# motor0.net
KiCad netlist of a schematic drawn in Altium Designer
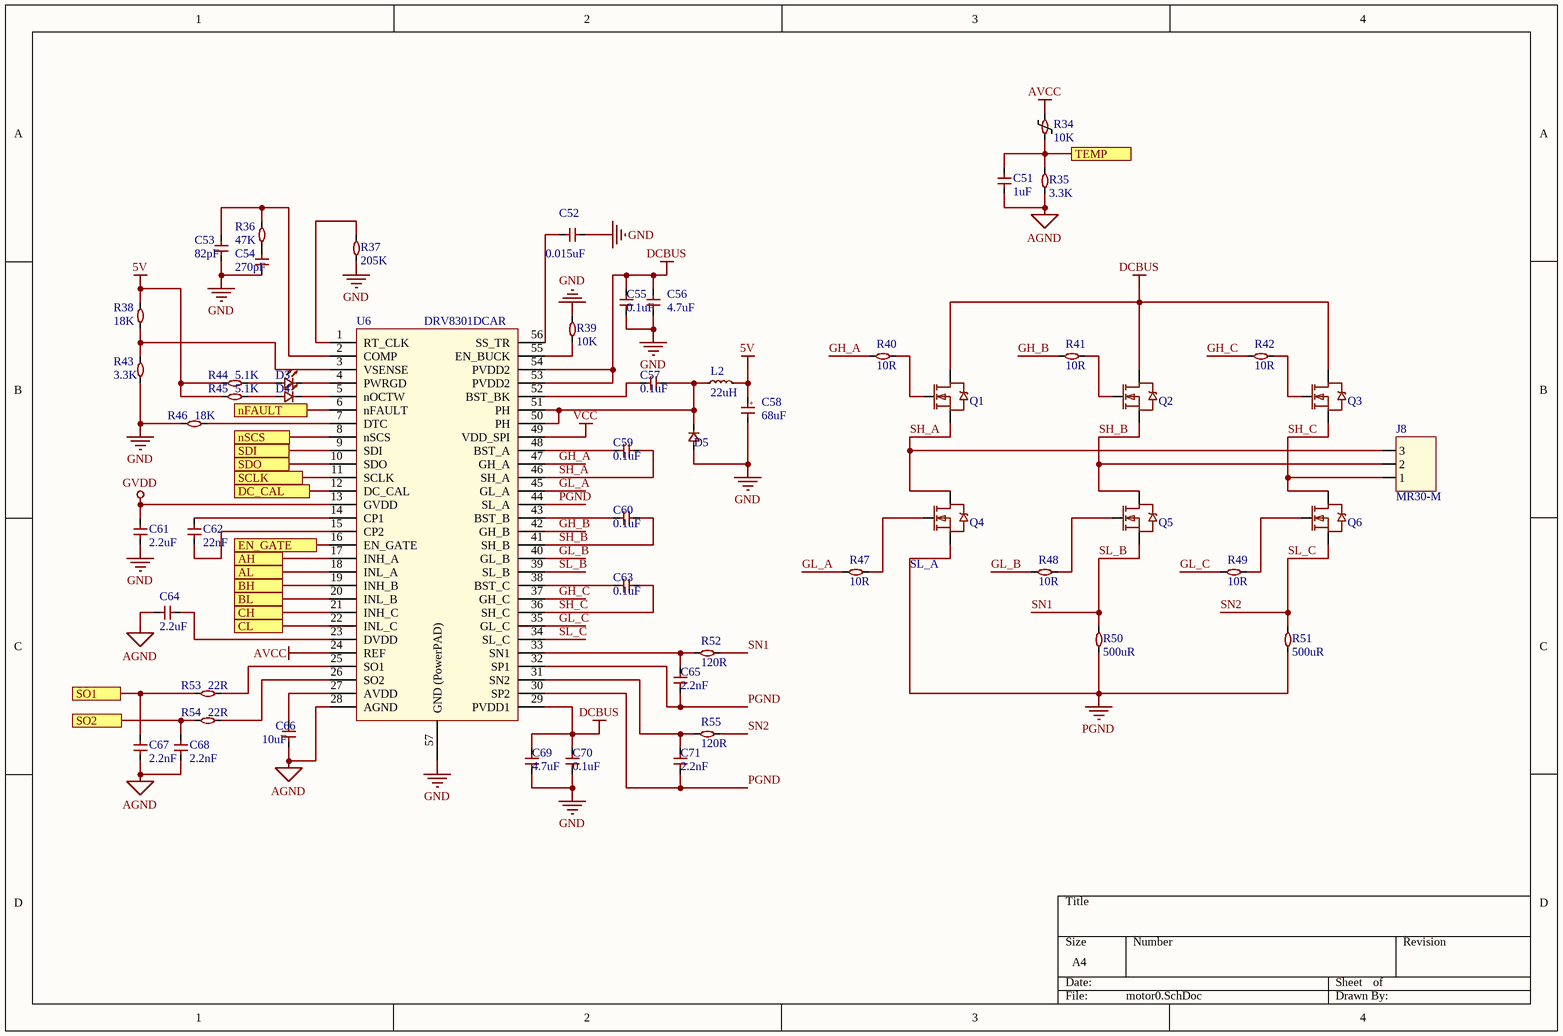
[diagram p0: motor0.SchDoc]

(export (version "E")
  (design (tool "Eeschema 10.0.6"))
  (components
    (comp (ref "C51")
      (value "1uF")
      (footprint "C0402")
      (description "贴片电容")
      (fields
        (field (name "MANUFACTURER") "SAMSUNG(三星)")
        (field (name "MANUFACTURER PART") "CL05A105KP5NNND")
      )
      (libsource (lib "schLibrary") (part "CAP"))
    )
    (comp (ref "C52")
      (value "0.015uF")
      (footprint "C0402")
      (description "贴片电容")
      (fields
        (field (name "MANUFACTURER") "SAMSUNG(三星)")
        (field (name "MANUFACTURER PART") "CL05A105KP5NNND")
      )
      (libsource (lib "schLibrary") (part "CAP"))
    )
    (comp (ref "C53")
      (value "82pF")
      (footprint "C0402")
      (description "贴片电容")
      (fields
        (field (name "MANUFACTURER") "SAMSUNG(三星)")
        (field (name "MANUFACTURER PART") "CL05A105KP5NNND")
      )
      (libsource (lib "schLibrary") (part "CAP"))
    )
    (comp (ref "C54")
      (value "270pF")
      (footprint "C0402")
      (description "贴片电容")
      (fields
        (field (name "MANUFACTURER") "SAMSUNG(三星)")
        (field (name "MANUFACTURER PART") "CL05A105KP5NNND")
      )
      (libsource (lib "schLibrary") (part "CAP"))
    )
    (comp (ref "C55")
      (value "0.1uF")
      (footprint "C0402")
      (description "贴片电容")
      (fields
        (field (name "MANUFACTURER") "SAMSUNG(三星)")
        (field (name "MANUFACTURER PART") "CL05A105KP5NNND")
      )
      (libsource (lib "schLibrary") (part "CAP"))
    )
    (comp (ref "C56")
      (value "4.7uF")
      (footprint "C0402")
      (description "贴片电容")
      (fields
        (field (name "MANUFACTURER") "SAMSUNG(三星)")
        (field (name "MANUFACTURER PART") "CL05A105KP5NNND")
      )
      (libsource (lib "schLibrary") (part "CAP"))
    )
    (comp (ref "C57")
      (value "0.1uF")
      (footprint "C0402")
      (description "贴片电容")
      (fields
        (field (name "MANUFACTURER") "SAMSUNG(三星)")
        (field (name "MANUFACTURER PART") "CL05A105KP5NNND")
      )
      (libsource (lib "schLibrary") (part "CAP"))
    )
    (comp (ref "C58")
      (value "68uF")
      (footprint "C1206")
      (description "贴片型铝电解电容，50V")
      (fields
        (field (name "MANUFACTURER") "SAMSUNG(三星)")
        (field (name "MANUFACTURER PART") "CL05A105KP5NNND")
      )
      (libsource (lib "schLibrary") (part "CAP+"))
    )
    (comp (ref "C59")
      (value "0.1uF")
      (footprint "C0402")
      (description "贴片电容")
      (fields
        (field (name "MANUFACTURER") "SAMSUNG(三星)")
        (field (name "MANUFACTURER PART") "CL05A105KP5NNND")
      )
      (libsource (lib "schLibrary") (part "CAP"))
    )
    (comp (ref "C60")
      (value "0.1uF")
      (footprint "C0402")
      (description "贴片电容")
      (fields
        (field (name "MANUFACTURER") "SAMSUNG(三星)")
        (field (name "MANUFACTURER PART") "CL05A105KP5NNND")
      )
      (libsource (lib "schLibrary") (part "CAP"))
    )
    (comp (ref "C61")
      (value "2.2uF")
      (footprint "C0402")
      (description "贴片电容")
      (fields
        (field (name "MANUFACTURER") "SAMSUNG(三星)")
        (field (name "MANUFACTURER PART") "CL05A105KP5NNND")
      )
      (libsource (lib "schLibrary") (part "CAP"))
    )
    (comp (ref "C62")
      (value "22nF")
      (footprint "C0402")
      (description "贴片电容")
      (fields
        (field (name "MANUFACTURER") "SAMSUNG(三星)")
        (field (name "MANUFACTURER PART") "CL05A105KP5NNND")
      )
      (libsource (lib "schLibrary") (part "CAP"))
    )
    (comp (ref "C63")
      (value "0.1uF")
      (footprint "C0402")
      (description "贴片电容")
      (fields
        (field (name "MANUFACTURER") "SAMSUNG(三星)")
        (field (name "MANUFACTURER PART") "CL05A105KP5NNND")
      )
      (libsource (lib "schLibrary") (part "CAP"))
    )
    (comp (ref "C64")
      (value "2.2uF")
      (footprint "C0402")
      (description "贴片电容")
      (fields
        (field (name "MANUFACTURER") "SAMSUNG(三星)")
        (field (name "MANUFACTURER PART") "CL05A105KP5NNND")
      )
      (libsource (lib "schLibrary") (part "CAP"))
    )
    (comp (ref "C65")
      (value "2.2nF")
      (footprint "C0402")
      (description "贴片电容")
      (fields
        (field (name "MANUFACTURER") "SAMSUNG(三星)")
        (field (name "MANUFACTURER PART") "CL05A105KP5NNND")
      )
      (libsource (lib "schLibrary") (part "CAP"))
    )
    (comp (ref "C66")
      (value "10uF")
      (footprint "C0402")
      (description "贴片电容")
      (fields
        (field (name "MANUFACTURER") "SAMSUNG(三星)")
        (field (name "MANUFACTURER PART") "CL05A105KP5NNND")
      )
      (libsource (lib "schLibrary") (part "CAP"))
    )
    (comp (ref "C67")
      (value "2.2nF")
      (footprint "C0402")
      (description "贴片电容")
      (fields
        (field (name "MANUFACTURER") "SAMSUNG(三星)")
        (field (name "MANUFACTURER PART") "CL05A105KP5NNND")
      )
      (libsource (lib "schLibrary") (part "CAP"))
    )
    (comp (ref "C68")
      (value "2.2nF")
      (footprint "C0402")
      (description "贴片电容")
      (fields
        (field (name "MANUFACTURER") "SAMSUNG(三星)")
        (field (name "MANUFACTURER PART") "CL05A105KP5NNND")
      )
      (libsource (lib "schLibrary") (part "CAP"))
    )
    (comp (ref "C69")
      (value "4.7uF")
      (footprint "C0402")
      (description "贴片电容")
      (fields
        (field (name "MANUFACTURER") "SAMSUNG(三星)")
        (field (name "MANUFACTURER PART") "CL05A105KP5NNND")
      )
      (libsource (lib "schLibrary") (part "CAP"))
    )
    (comp (ref "C70")
      (value "0.1uF")
      (footprint "C0402")
      (description "贴片电容")
      (fields
        (field (name "MANUFACTURER") "SAMSUNG(三星)")
        (field (name "MANUFACTURER PART") "CL05A105KP5NNND")
      )
      (libsource (lib "schLibrary") (part "CAP"))
    )
    (comp (ref "C71")
      (value "2.2nF")
      (footprint "C0402")
      (description "贴片电容")
      (fields
        (field (name "MANUFACTURER") "SAMSUNG(三星)")
        (field (name "MANUFACTURER PART") "CL05A105KP5NNND")
      )
      (libsource (lib "schLibrary") (part "CAP"))
    )
    (comp (ref "D3")
      (value "LED")
      (footprint "LED-0402")
      (description "贴片发光二极管")
      (fields
        (field (name "MANUFACTURER") "SAMSUNG(三星)")
        (field (name "MANUFACTURER PART") "CL05A105KP5NNND")
      )
      (libsource (lib "schLibrary") (part "LED"))
    )
    (comp (ref "D4")
      (value "LED")
      (footprint "LED-0402")
      (description "贴片发光二极管")
      (fields
        (field (name "MANUFACTURER") "SAMSUNG(三星)")
        (field (name "MANUFACTURER PART") "CL05A105KP5NNND")
      )
      (libsource (lib "schLibrary") (part "LED"))
    )
    (comp (ref "D5")
      (value "MBR0540")
      (footprint "SOD-323")
      (description "肖特基二极管")
      (fields
        (field (name "MANUFACTURER") "SAMSUNG(三星)")
        (field (name "MANUFACTURER PART") "CL05A105KP5NNND")
      )
      (libsource (lib "schLibrary") (part "DIO"))
    )
    (comp (ref "J8")
      (value "MR30-M")
      (footprint "AMASS-MR30-M")
      (description "线对板连接器")
      (libsource (lib "schLibrary") (part "HC-3P-1.0mm"))
    )
    (comp (ref "L2")
      (value "22uH")
      (footprint "L1008")
      (description "贴片电感")
      (libsource (lib "schLibrary") (part "IND"))
    )
    (comp (ref "Q1")
      (value "AP68N06G")
      (footprint "TDSON-8_L5.0-W6.0-3PIN")
      (description "N沟道功率mos管")
      (fields (field (name "MANUFACTURER") "BORN(伯恩半导体)") (field (name "MANUFACTURER PART") "AO3401A"))
      (libsource (lib "schLibrary") (part "NMOS"))
    )
    (comp (ref "Q2")
      (value "AP68N06G")
      (footprint "TDSON-8_L5.0-W6.0-3PIN")
      (description "N沟道功率mos管")
      (fields (field (name "MANUFACTURER") "BORN(伯恩半导体)") (field (name "MANUFACTURER PART") "AO3401A"))
      (libsource (lib "schLibrary") (part "NMOS"))
    )
    (comp (ref "Q3")
      (value "AP68N06G")
      (footprint "TDSON-8_L5.0-W6.0-3PIN")
      (description "N沟道功率mos管")
      (fields (field (name "MANUFACTURER") "BORN(伯恩半导体)") (field (name "MANUFACTURER PART") "AO3401A"))
      (libsource (lib "schLibrary") (part "NMOS"))
    )
    (comp (ref "Q4")
      (value "AP68N06G")
      (footprint "TDSON-8_L5.0-W6.0-3PIN")
      (description "N沟道功率mos管")
      (fields (field (name "MANUFACTURER") "BORN(伯恩半导体)") (field (name "MANUFACTURER PART") "AO3401A"))
      (libsource (lib "schLibrary") (part "NMOS"))
    )
    (comp (ref "Q5")
      (value "AP68N06G")
      (footprint "TDSON-8_L5.0-W6.0-3PIN")
      (description "N沟道功率mos管")
      (fields (field (name "MANUFACTURER") "BORN(伯恩半导体)") (field (name "MANUFACTURER PART") "AO3401A"))
      (libsource (lib "schLibrary") (part "NMOS"))
    )
    (comp (ref "Q6")
      (value "AP68N06G")
      (footprint "TDSON-8_L5.0-W6.0-3PIN")
      (description "N沟道功率mos管")
      (fields (field (name "MANUFACTURER") "BORN(伯恩半导体)") (field (name "MANUFACTURER PART") "AO3401A"))
      (libsource (lib "schLibrary") (part "NMOS"))
    )
    (comp (ref "R34")
      (value "10K")
      (footprint "R0402")
      (description "热敏电阻")
      (fields
        (field (name "MANUFACTURER") "UNI-ROYAL(厚声)")
        (field (name "MANUFACTURER PART") "0402WGF1001TCE")
      )
      (libsource (lib "schLibrary") (part "NTC"))
    )
    (comp (ref "R35")
      (value "3.3K")
      (footprint "R0402")
      (description "贴片电阻")
      (fields
        (field (name "MANUFACTURER") "UNI-ROYAL(厚声)")
        (field (name "MANUFACTURER PART") "0402WGF1001TCE")
      )
      (libsource (lib "schLibrary") (part "RES"))
    )
    (comp (ref "R36")
      (value "47K")
      (footprint "R0402")
      (description "贴片电阻")
      (fields
        (field (name "MANUFACTURER") "UNI-ROYAL(厚声)")
        (field (name "MANUFACTURER PART") "0402WGF1001TCE")
      )
      (libsource (lib "schLibrary") (part "RES"))
    )
    (comp (ref "R37")
      (value "205K")
      (footprint "R0402")
      (description "贴片电阻")
      (fields
        (field (name "MANUFACTURER") "UNI-ROYAL(厚声)")
        (field (name "MANUFACTURER PART") "0402WGF1001TCE")
      )
      (libsource (lib "schLibrary") (part "RES"))
    )
    (comp (ref "R38")
      (value "18K")
      (footprint "R0402")
      (description "贴片电阻")
      (fields
        (field (name "MANUFACTURER") "UNI-ROYAL(厚声)")
        (field (name "MANUFACTURER PART") "0402WGF1001TCE")
      )
      (libsource (lib "schLibrary") (part "RES"))
    )
    (comp (ref "R39")
      (value "10K")
      (footprint "R0402")
      (description "贴片电阻")
      (fields
        (field (name "MANUFACTURER") "UNI-ROYAL(厚声)")
        (field (name "MANUFACTURER PART") "0402WGF1001TCE")
      )
      (libsource (lib "schLibrary") (part "RES"))
    )
    (comp (ref "R40")
      (value "10R")
      (footprint "R0402")
      (description "贴片电阻")
      (fields
        (field (name "MANUFACTURER") "UNI-ROYAL(厚声)")
        (field (name "MANUFACTURER PART") "0402WGF1001TCE")
      )
      (libsource (lib "schLibrary") (part "RES"))
    )
    (comp (ref "R41")
      (value "10R")
      (footprint "R0402")
      (description "贴片电阻")
      (fields
        (field (name "MANUFACTURER") "UNI-ROYAL(厚声)")
        (field (name "MANUFACTURER PART") "0402WGF1001TCE")
      )
      (libsource (lib "schLibrary") (part "RES"))
    )
    (comp (ref "R42")
      (value "10R")
      (footprint "R0402")
      (description "贴片电阻")
      (fields
        (field (name "MANUFACTURER") "UNI-ROYAL(厚声)")
        (field (name "MANUFACTURER PART") "0402WGF1001TCE")
      )
      (libsource (lib "schLibrary") (part "RES"))
    )
    (comp (ref "R43")
      (value "3.3K")
      (footprint "R0402")
      (description "贴片电阻")
      (fields
        (field (name "MANUFACTURER") "UNI-ROYAL(厚声)")
        (field (name "MANUFACTURER PART") "0402WGF1001TCE")
      )
      (libsource (lib "schLibrary") (part "RES"))
    )
    (comp (ref "R44")
      (value "5.1K")
      (footprint "R0402")
      (description "贴片电阻")
      (fields
        (field (name "MANUFACTURER") "UNI-ROYAL(厚声)")
        (field (name "MANUFACTURER PART") "0402WGF1001TCE")
      )
      (libsource (lib "schLibrary") (part "RES"))
    )
    (comp (ref "R45")
      (value "5.1K")
      (footprint "R0402")
      (description "贴片电阻")
      (fields
        (field (name "MANUFACTURER") "UNI-ROYAL(厚声)")
        (field (name "MANUFACTURER PART") "0402WGF1001TCE")
      )
      (libsource (lib "schLibrary") (part "RES"))
    )
    (comp (ref "R46")
      (value "18K")
      (footprint "R0402")
      (description "贴片电阻")
      (fields
        (field (name "MANUFACTURER") "UNI-ROYAL(厚声)")
        (field (name "MANUFACTURER PART") "0402WGF1001TCE")
      )
      (libsource (lib "schLibrary") (part "RES"))
    )
    (comp (ref "R47")
      (value "10R")
      (footprint "R0402")
      (description "贴片电阻")
      (fields
        (field (name "MANUFACTURER") "UNI-ROYAL(厚声)")
        (field (name "MANUFACTURER PART") "0402WGF1001TCE")
      )
      (libsource (lib "schLibrary") (part "RES"))
    )
    (comp (ref "R48")
      (value "10R")
      (footprint "R0402")
      (description "贴片电阻")
      (fields
        (field (name "MANUFACTURER") "UNI-ROYAL(厚声)")
        (field (name "MANUFACTURER PART") "0402WGF1001TCE")
      )
      (libsource (lib "schLibrary") (part "RES"))
    )
    (comp (ref "R49")
      (value "10R")
      (footprint "R0402")
      (description "贴片电阻")
      (fields
        (field (name "MANUFACTURER") "UNI-ROYAL(厚声)")
        (field (name "MANUFACTURER PART") "0402WGF1001TCE")
      )
      (libsource (lib "schLibrary") (part "RES"))
    )
    (comp (ref "R50")
      (value "500uR")
      (footprint "R2512")
      (description "贴片电阻 2512")
      (fields
        (field (name "MANUFACTURER") "UNI-ROYAL(厚声)")
        (field (name "MANUFACTURER PART") "0402WGF1001TCE")
      )
      (libsource (lib "schLibrary") (part "RES"))
    )
    (comp (ref "R51")
      (value "500uR")
      (footprint "R2512")
      (description "贴片电阻\r\n2512")
      (fields
        (field (name "MANUFACTURER") "UNI-ROYAL(厚声)")
        (field (name "MANUFACTURER PART") "0402WGF1001TCE")
      )
      (libsource (lib "schLibrary") (part "RES"))
    )
    (comp (ref "R52")
      (value "120R")
      (footprint "R0402")
      (description "贴片电阻")
      (fields
        (field (name "MANUFACTURER") "UNI-ROYAL(厚声)")
        (field (name "MANUFACTURER PART") "0402WGF1001TCE")
      )
      (libsource (lib "schLibrary") (part "RES"))
    )
    (comp (ref "R53")
      (value "22R")
      (footprint "R0402")
      (description "贴片电阻")
      (fields
        (field (name "MANUFACTURER") "UNI-ROYAL(厚声)")
        (field (name "MANUFACTURER PART") "0402WGF1001TCE")
      )
      (libsource (lib "schLibrary") (part "RES"))
    )
    (comp (ref "R54")
      (value "22R")
      (footprint "R0402")
      (description "贴片电阻")
      (fields
        (field (name "MANUFACTURER") "UNI-ROYAL(厚声)")
        (field (name "MANUFACTURER PART") "0402WGF1001TCE")
      )
      (libsource (lib "schLibrary") (part "RES"))
    )
    (comp (ref "R55")
      (value "120R")
      (footprint "R0402")
      (description "贴片电阻")
      (fields
        (field (name "MANUFACTURER") "UNI-ROYAL(厚声)")
        (field (name "MANUFACTURER PART") "0402WGF1001TCE")
      )
      (libsource (lib "schLibrary") (part "RES"))
    )
    (comp (ref "U6")
      (value "DRV8301DCAR")
      (footprint "HTSSOP-56_L14.0-W6.0-P0.50")
      (description "三相电机/栅极驱动IC")
      (libsource (lib "schLibrary") (part "DRV8301DCAR"))
    )
  )
  (nets
    (net (code "1") (name "/AH") (class "Default")
      (node (ref "U6") (pin "17") (pinfunction "INH_A_17") (pintype "passive"))
    )
    (net (code "2") (name "/AL") (class "Default")
      (node (ref "U6") (pin "18") (pinfunction "INL_A_18") (pintype "passive"))
    )
    (net (code "3") (name "/BH") (class "Default")
      (node (ref "U6") (pin "19") (pinfunction "INH_B_19") (pintype "passive"))
    )
    (net (code "4") (name "/BL") (class "Default")
      (node (ref "U6") (pin "20") (pinfunction "INL_B_20") (pintype "passive"))
    )
    (net (code "5") (name "/CH") (class "Default")
      (node (ref "U6") (pin "21") (pinfunction "INH_C_21") (pintype "passive"))
    )
    (net (code "6") (name "/CL") (class "Default")
      (node (ref "U6") (pin "22") (pinfunction "INL_C_22") (pintype "passive"))
    )
    (net (code "7") (name "/DC_CAL") (class "Default")
      (node (ref "U6") (pin "12") (pinfunction "DC_CAL_12") (pintype "passive"))
    )
    (net (code "8") (name "/EN_GATE") (class "Default")
      (node (ref "U6") (pin "16") (pinfunction "EN_GATE_16") (pintype "passive"))
    )
    (net (code "9") (name "/GH_A") (class "Default")
      (node (ref "R40") (pin "2") (pinfunction "2_2") (pintype "passive"))
      (node (ref "U6") (pin "47") (pinfunction "GH_A_47") (pintype "passive"))
    )
    (net (code "10") (name "/GH_B") (class "Default")
      (node (ref "R41") (pin "2") (pinfunction "2_2") (pintype "passive"))
      (node (ref "U6") (pin "42") (pinfunction "GH_B_42") (pintype "passive"))
    )
    (net (code "11") (name "/GH_C") (class "Default")
      (node (ref "R42") (pin "2") (pinfunction "2_2") (pintype "passive"))
      (node (ref "U6") (pin "37") (pinfunction "GH_C_37") (pintype "passive"))
    )
    (net (code "12") (name "/GL_A") (class "Default")
      (node (ref "R47") (pin "2") (pinfunction "2_2") (pintype "passive"))
      (node (ref "U6") (pin "45") (pinfunction "GL_A_45") (pintype "passive"))
    )
    (net (code "13") (name "/GL_B") (class "Default")
      (node (ref "R48") (pin "2") (pinfunction "2_2") (pintype "passive"))
      (node (ref "U6") (pin "40") (pinfunction "GL_B_40") (pintype "passive"))
    )
    (net (code "14") (name "/GL_C") (class "Default")
      (node (ref "R49") (pin "2") (pinfunction "2_2") (pintype "passive"))
      (node (ref "U6") (pin "35") (pinfunction "GL_C_35") (pintype "passive"))
    )
    (net (code "15") (name "/SCLK") (class "Default")
      (node (ref "U6") (pin "11") (pinfunction "SCLK_11") (pintype "passive"))
    )
    (net (code "16") (name "/SDI") (class "Default")
      (node (ref "U6") (pin "9") (pinfunction "SDI_9") (pintype "passive"))
    )
    (net (code "17") (name "/SDO") (class "Default")
      (node (ref "U6") (pin "10") (pinfunction "SDO_10") (pintype "passive"))
    )
    (net (code "18") (name "/SH_A") (class "Default")
      (node (ref "C59") (pin "2") (pinfunction "2_2") (pintype "passive"))
      (node (ref "J8") (pin "3") (pinfunction "3_3") (pintype "passive"))
      (node (ref "Q1") (pin "2") (pinfunction "S_2") (pintype "passive"))
      (node (ref "Q4") (pin "3") (pinfunction "D_3") (pintype "passive"))
      (node (ref "U6") (pin "46") (pinfunction "SH_A_46") (pintype "passive"))
    )
    (net (code "19") (name "/SH_B") (class "Default")
      (node (ref "C60") (pin "2") (pinfunction "2_2") (pintype "passive"))
      (node (ref "J8") (pin "2") (pinfunction "2_2") (pintype "passive"))
      (node (ref "Q2") (pin "2") (pinfunction "S_2") (pintype "passive"))
      (node (ref "Q5") (pin "3") (pinfunction "D_3") (pintype "passive"))
      (node (ref "U6") (pin "41") (pinfunction "SH_B_41") (pintype "passive"))
    )
    (net (code "20") (name "/SH_C") (class "Default")
      (node (ref "C63") (pin "2") (pinfunction "2_2") (pintype "passive"))
      (node (ref "J8") (pin "1") (pinfunction "1_1") (pintype "passive"))
      (node (ref "Q3") (pin "2") (pinfunction "S_2") (pintype "passive"))
      (node (ref "Q6") (pin "3") (pinfunction "D_3") (pintype "passive"))
      (node (ref "U6") (pin "36") (pinfunction "SH_C_36") (pintype "passive"))
    )
    (net (code "21") (name "/SL_B") (class "Default")
      (node (ref "Q5") (pin "2") (pinfunction "S_2") (pintype "passive"))
      (node (ref "R50") (pin "1") (pinfunction "1_1") (pintype "passive"))
      (node (ref "R52") (pin "2") (pinfunction "2_2") (pintype "passive"))
      (node (ref "U6") (pin "39") (pinfunction "SL_B_39") (pintype "passive"))
    )
    (net (code "22") (name "/SL_C") (class "Default")
      (node (ref "Q6") (pin "2") (pinfunction "S_2") (pintype "passive"))
      (node (ref "R51") (pin "1") (pinfunction "1_1") (pintype "passive"))
      (node (ref "R55") (pin "2") (pinfunction "2_2") (pintype "passive"))
      (node (ref "U6") (pin "34") (pinfunction "SL_C_34") (pintype "passive"))
    )
    (net (code "23") (name "/SO1") (class "Default")
      (node (ref "C67") (pin "1") (pinfunction "1_1") (pintype "passive"))
      (node (ref "R53") (pin "1") (pinfunction "1_1") (pintype "passive"))
    )
    (net (code "24") (name "/SO2") (class "Default")
      (node (ref "C68") (pin "1") (pinfunction "1_1") (pintype "passive"))
      (node (ref "R54") (pin "1") (pinfunction "1_1") (pintype "passive"))
    )
    (net (code "25") (name "/TEMP") (class "Default")
      (node (ref "C51") (pin "1") (pinfunction "1_1") (pintype "passive"))
      (node (ref "R34") (pin "1") (pinfunction "1_1") (pintype "passive"))
      (node (ref "R35") (pin "2") (pinfunction "2_2") (pintype "passive"))
    )
    (net (code "26") (name "/nFAULT") (class "Default")
      (node (ref "U6") (pin "6") (pinfunction "nFAULT_6") (pintype "passive"))
    )
    (net (code "27") (name "/nSCS") (class "Default")
      (node (ref "U6") (pin "8") (pinfunction "nSCS_8") (pintype "passive"))
    )
    (net (code "28") (name "5V") (class "Default")
      (node (ref "C58") (pin "1") (pinfunction "1_1") (pintype "passive"))
      (node (ref "L2") (pin "2") (pinfunction "2_2") (pintype "passive"))
      (node (ref "R38") (pin "2") (pinfunction "2_2") (pintype "passive"))
      (node (ref "R44") (pin "1") (pinfunction "1_1") (pintype "passive"))
      (node (ref "R45") (pin "1") (pinfunction "1_1") (pintype "passive"))
    )
    (net (code "29") (name "AGND") (class "Default")
      (node (ref "C51") (pin "2") (pinfunction "2_2") (pintype "passive"))
      (node (ref "C64") (pin "1") (pinfunction "1_1") (pintype "passive"))
      (node (ref "C66") (pin "2") (pinfunction "2_2") (pintype "passive"))
      (node (ref "C67") (pin "2") (pinfunction "2_2") (pintype "passive"))
      (node (ref "C68") (pin "2") (pinfunction "2_2") (pintype "passive"))
      (node (ref "R35") (pin "1") (pinfunction "1_1") (pintype "passive"))
      (node (ref "U6") (pin "28") (pinfunction "AGND_28") (pintype "passive"))
    )
    (net (code "30") (name "AVCC") (class "Default")
      (node (ref "R34") (pin "2") (pinfunction "2_2") (pintype "passive"))
      (node (ref "U6") (pin "24") (pinfunction "REF_24") (pintype "passive"))
    )
    (net (code "31") (name "DCBUS") (class "Default")
      (node (ref "C55") (pin "1") (pinfunction "1_1") (pintype "passive"))
      (node (ref "C56") (pin "1") (pinfunction "1_1") (pintype "passive"))
      (node (ref "C69") (pin "1") (pinfunction "1_1") (pintype "passive"))
      (node (ref "C70") (pin "1") (pinfunction "1_1") (pintype "passive"))
      (node (ref "Q1") (pin "3") (pinfunction "D_3") (pintype "passive"))
      (node (ref "Q2") (pin "3") (pinfunction "D_3") (pintype "passive"))
      (node (ref "Q3") (pin "3") (pinfunction "D_3") (pintype "passive"))
      (node (ref "U6") (pin "29") (pinfunction "PVDD1_29") (pintype "passive"))
      (node (ref "U6") (pin "53") (pinfunction "PVDD2_53") (pintype "passive"))
      (node (ref "U6") (pin "54") (pinfunction "PVDD2_54") (pintype "passive"))
    )
    (net (code "32") (name "GND") (class "Default")
      (node (ref "C52") (pin "2") (pinfunction "2_2") (pintype "passive"))
      (node (ref "C53") (pin "1") (pinfunction "1_1") (pintype "passive"))
      (node (ref "C54") (pin "1") (pinfunction "1_1") (pintype "passive"))
      (node (ref "C55") (pin "2") (pinfunction "2_2") (pintype "passive"))
      (node (ref "C56") (pin "2") (pinfunction "2_2") (pintype "passive"))
      (node (ref "C58") (pin "2") (pinfunction "2_2") (pintype "passive"))
      (node (ref "C61") (pin "1") (pinfunction "1_1") (pintype "passive"))
      (node (ref "C69") (pin "2") (pinfunction "2_2") (pintype "passive"))
      (node (ref "C70") (pin "2") (pinfunction "2_2") (pintype "passive"))
      (node (ref "D5") (pin "2") (pinfunction "2_2") (pintype "passive"))
      (node (ref "R37") (pin "2") (pinfunction "2_2") (pintype "passive"))
      (node (ref "R39") (pin "2") (pinfunction "2_2") (pintype "passive"))
      (node (ref "R43") (pin "1") (pinfunction "1_1") (pintype "passive"))
      (node (ref "R46") (pin "1") (pinfunction "1_1") (pintype "passive"))
      (node (ref "U6") (pin "57") (pinfunction "GND_(PowerPAD)_57") (pintype "passive"))
    )
    (net (code "33") (name "GVDD") (class "Default")
      (node (ref "C61") (pin "2") (pinfunction "2_2") (pintype "passive"))
      (node (ref "U6") (pin "13") (pinfunction "GVDD_13") (pintype "passive"))
    )
    (net (code "34") (name "Net-(C54-Pad2)") (class "Default")
      (node (ref "C54") (pin "2") (pinfunction "2_2") (pintype "passive"))
      (node (ref "R36") (pin "2") (pinfunction "2_2") (pintype "passive"))
    )
    (net (code "35") (name "Net-(C57-Pad2)") (class "Default")
      (node (ref "C57") (pin "2") (pinfunction "2_2") (pintype "passive"))
      (node (ref "D5") (pin "1") (pinfunction "1_1") (pintype "passive"))
      (node (ref "L2") (pin "1") (pinfunction "1_1") (pintype "passive"))
      (node (ref "U6") (pin "50") (pinfunction "PH_50") (pintype "passive"))
      (node (ref "U6") (pin "51") (pinfunction "PH_51") (pintype "passive"))
    )
    (net (code "36") (name "Net-(D3-Pad2)") (class "Default")
      (node (ref "D3") (pin "2") (pinfunction "2_2") (pintype "passive"))
      (node (ref "R44") (pin "2") (pinfunction "2_2") (pintype "passive"))
    )
    (net (code "37") (name "Net-(D4-Pad2)") (class "Default")
      (node (ref "D4") (pin "2") (pinfunction "2_2") (pintype "passive"))
      (node (ref "R45") (pin "2") (pinfunction "2_2") (pintype "passive"))
    )
    (net (code "38") (name "Net-(Q1-G)") (class "Default")
      (node (ref "Q1") (pin "1") (pinfunction "G_1") (pintype "passive"))
      (node (ref "R40") (pin "1") (pinfunction "1_1") (pintype "passive"))
    )
    (net (code "39") (name "Net-(Q2-G)") (class "Default")
      (node (ref "Q2") (pin "1") (pinfunction "G_1") (pintype "passive"))
      (node (ref "R41") (pin "1") (pinfunction "1_1") (pintype "passive"))
    )
    (net (code "40") (name "Net-(Q3-G)") (class "Default")
      (node (ref "Q3") (pin "1") (pinfunction "G_1") (pintype "passive"))
      (node (ref "R42") (pin "1") (pinfunction "1_1") (pintype "passive"))
    )
    (net (code "41") (name "Net-(Q4-G)") (class "Default")
      (node (ref "Q4") (pin "1") (pinfunction "G_1") (pintype "passive"))
      (node (ref "R47") (pin "1") (pinfunction "1_1") (pintype "passive"))
    )
    (net (code "42") (name "Net-(Q5-G)") (class "Default")
      (node (ref "Q5") (pin "1") (pinfunction "G_1") (pintype "passive"))
      (node (ref "R48") (pin "1") (pinfunction "1_1") (pintype "passive"))
    )
    (net (code "43") (name "Net-(Q6-G)") (class "Default")
      (node (ref "Q6") (pin "1") (pinfunction "G_1") (pintype "passive"))
      (node (ref "R49") (pin "1") (pinfunction "1_1") (pintype "passive"))
    )
    (net (code "44") (name "Net-(U6-AVDD)") (class "Default")
      (node (ref "C66") (pin "1") (pinfunction "1_1") (pintype "passive"))
      (node (ref "U6") (pin "27") (pinfunction "AVDD_27") (pintype "passive"))
    )
    (net (code "45") (name "Net-(U6-BST_A)") (class "Default")
      (node (ref "C59") (pin "1") (pinfunction "1_1") (pintype "passive"))
      (node (ref "U6") (pin "48") (pinfunction "BST_A_48") (pintype "passive"))
    )
    (net (code "46") (name "Net-(U6-BST_B)") (class "Default")
      (node (ref "C60") (pin "1") (pinfunction "1_1") (pintype "passive"))
      (node (ref "U6") (pin "43") (pinfunction "BST_B_43") (pintype "passive"))
    )
    (net (code "47") (name "Net-(U6-BST_BK)") (class "Default")
      (node (ref "C57") (pin "1") (pinfunction "1_1") (pintype "passive"))
      (node (ref "U6") (pin "52") (pinfunction "BST_BK_52") (pintype "passive"))
    )
    (net (code "48") (name "Net-(U6-BST_C)") (class "Default")
      (node (ref "C63") (pin "1") (pinfunction "1_1") (pintype "passive"))
      (node (ref "U6") (pin "38") (pinfunction "BST_C_38") (pintype "passive"))
    )
    (net (code "49") (name "Net-(U6-COMP)") (class "Default")
      (node (ref "C53") (pin "2") (pinfunction "2_2") (pintype "passive"))
      (node (ref "R36") (pin "1") (pinfunction "1_1") (pintype "passive"))
      (node (ref "U6") (pin "2") (pinfunction "COMP_2") (pintype "passive"))
    )
    (net (code "50") (name "Net-(U6-CP1)") (class "Default")
      (node (ref "C62") (pin "2") (pinfunction "2_2") (pintype "passive"))
      (node (ref "U6") (pin "14") (pinfunction "CP1_14") (pintype "passive"))
    )
    (net (code "51") (name "Net-(U6-CP2)") (class "Default")
      (node (ref "C62") (pin "1") (pinfunction "1_1") (pintype "passive"))
      (node (ref "U6") (pin "15") (pinfunction "CP2_15") (pintype "passive"))
    )
    (net (code "52") (name "Net-(U6-DTC)") (class "Default")
      (node (ref "R46") (pin "2") (pinfunction "2_2") (pintype "passive"))
      (node (ref "U6") (pin "7") (pinfunction "DTC_7") (pintype "passive"))
    )
    (net (code "53") (name "Net-(U6-DVDD)") (class "Default")
      (node (ref "C64") (pin "2") (pinfunction "2_2") (pintype "passive"))
      (node (ref "U6") (pin "23") (pinfunction "DVDD_23") (pintype "passive"))
    )
    (net (code "54") (name "Net-(U6-EN_BUCK)") (class "Default")
      (node (ref "R39") (pin "1") (pinfunction "1_1") (pintype "passive"))
      (node (ref "U6") (pin "55") (pinfunction "EN_BUCK_55") (pintype "passive"))
    )
    (net (code "55") (name "Net-(U6-PWRGD)") (class "Default")
      (node (ref "D3") (pin "1") (pinfunction "1_1") (pintype "passive"))
      (node (ref "U6") (pin "4") (pinfunction "PWRGD_4") (pintype "passive"))
    )
    (net (code "56") (name "Net-(U6-RT_CLK)") (class "Default")
      (node (ref "R37") (pin "1") (pinfunction "1_1") (pintype "passive"))
      (node (ref "U6") (pin "1") (pinfunction "RT_CLK_1") (pintype "passive"))
    )
    (net (code "57") (name "Net-(U6-SN1)") (class "Default")
      (node (ref "C65") (pin "1") (pinfunction "1_1") (pintype "passive"))
      (node (ref "R52") (pin "1") (pinfunction "1_1") (pintype "passive"))
      (node (ref "U6") (pin "33") (pinfunction "SN1_33") (pintype "passive"))
    )
    (net (code "58") (name "Net-(U6-SN2)") (class "Default")
      (node (ref "C71") (pin "1") (pinfunction "1_1") (pintype "passive"))
      (node (ref "R55") (pin "1") (pinfunction "1_1") (pintype "passive"))
      (node (ref "U6") (pin "31") (pinfunction "SN2_31") (pintype "passive"))
    )
    (net (code "59") (name "Net-(U6-SO1)") (class "Default")
      (node (ref "R53") (pin "2") (pinfunction "2_2") (pintype "passive"))
      (node (ref "U6") (pin "25") (pinfunction "SO1_25") (pintype "passive"))
    )
    (net (code "60") (name "Net-(U6-SO2)") (class "Default")
      (node (ref "R54") (pin "2") (pinfunction "2_2") (pintype "passive"))
      (node (ref "U6") (pin "26") (pinfunction "SO2_26") (pintype "passive"))
    )
    (net (code "61") (name "Net-(U6-SS_TR)") (class "Default")
      (node (ref "C52") (pin "1") (pinfunction "1_1") (pintype "passive"))
      (node (ref "U6") (pin "56") (pinfunction "SS_TR_56") (pintype "passive"))
    )
    (net (code "62") (name "Net-(U6-VSENSE)") (class "Default")
      (node (ref "R38") (pin "1") (pinfunction "1_1") (pintype "passive"))
      (node (ref "R43") (pin "2") (pinfunction "2_2") (pintype "passive"))
      (node (ref "U6") (pin "3") (pinfunction "VSENSE_3") (pintype "passive"))
    )
    (net (code "63") (name "Net-(U6-nOCTW)") (class "Default")
      (node (ref "D4") (pin "1") (pinfunction "1_1") (pintype "passive"))
      (node (ref "U6") (pin "5") (pinfunction "nOCTW_5") (pintype "passive"))
    )
    (net (code "64") (name "PGND") (class "Default")
      (node (ref "C65") (pin "2") (pinfunction "2_2") (pintype "passive"))
      (node (ref "C71") (pin "2") (pinfunction "2_2") (pintype "passive"))
      (node (ref "Q4") (pin "2") (pinfunction "S_2") (pintype "passive"))
      (node (ref "R50") (pin "2") (pinfunction "2_2") (pintype "passive"))
      (node (ref "R51") (pin "2") (pinfunction "2_2") (pintype "passive"))
      (node (ref "U6") (pin "30") (pinfunction "SP2_30") (pintype "passive"))
      (node (ref "U6") (pin "32") (pinfunction "SP1_32") (pintype "passive"))
      (node (ref "U6") (pin "44") (pinfunction "SL_A_44") (pintype "passive"))
    )
    (net (code "65") (name "VCC") (class "Default")
      (node (ref "U6") (pin "49") (pinfunction "VDD_SPI_49") (pintype "passive"))
    )
  )
)
